# design.net
KiCad netlist of a schematic drawn in Altium Designer
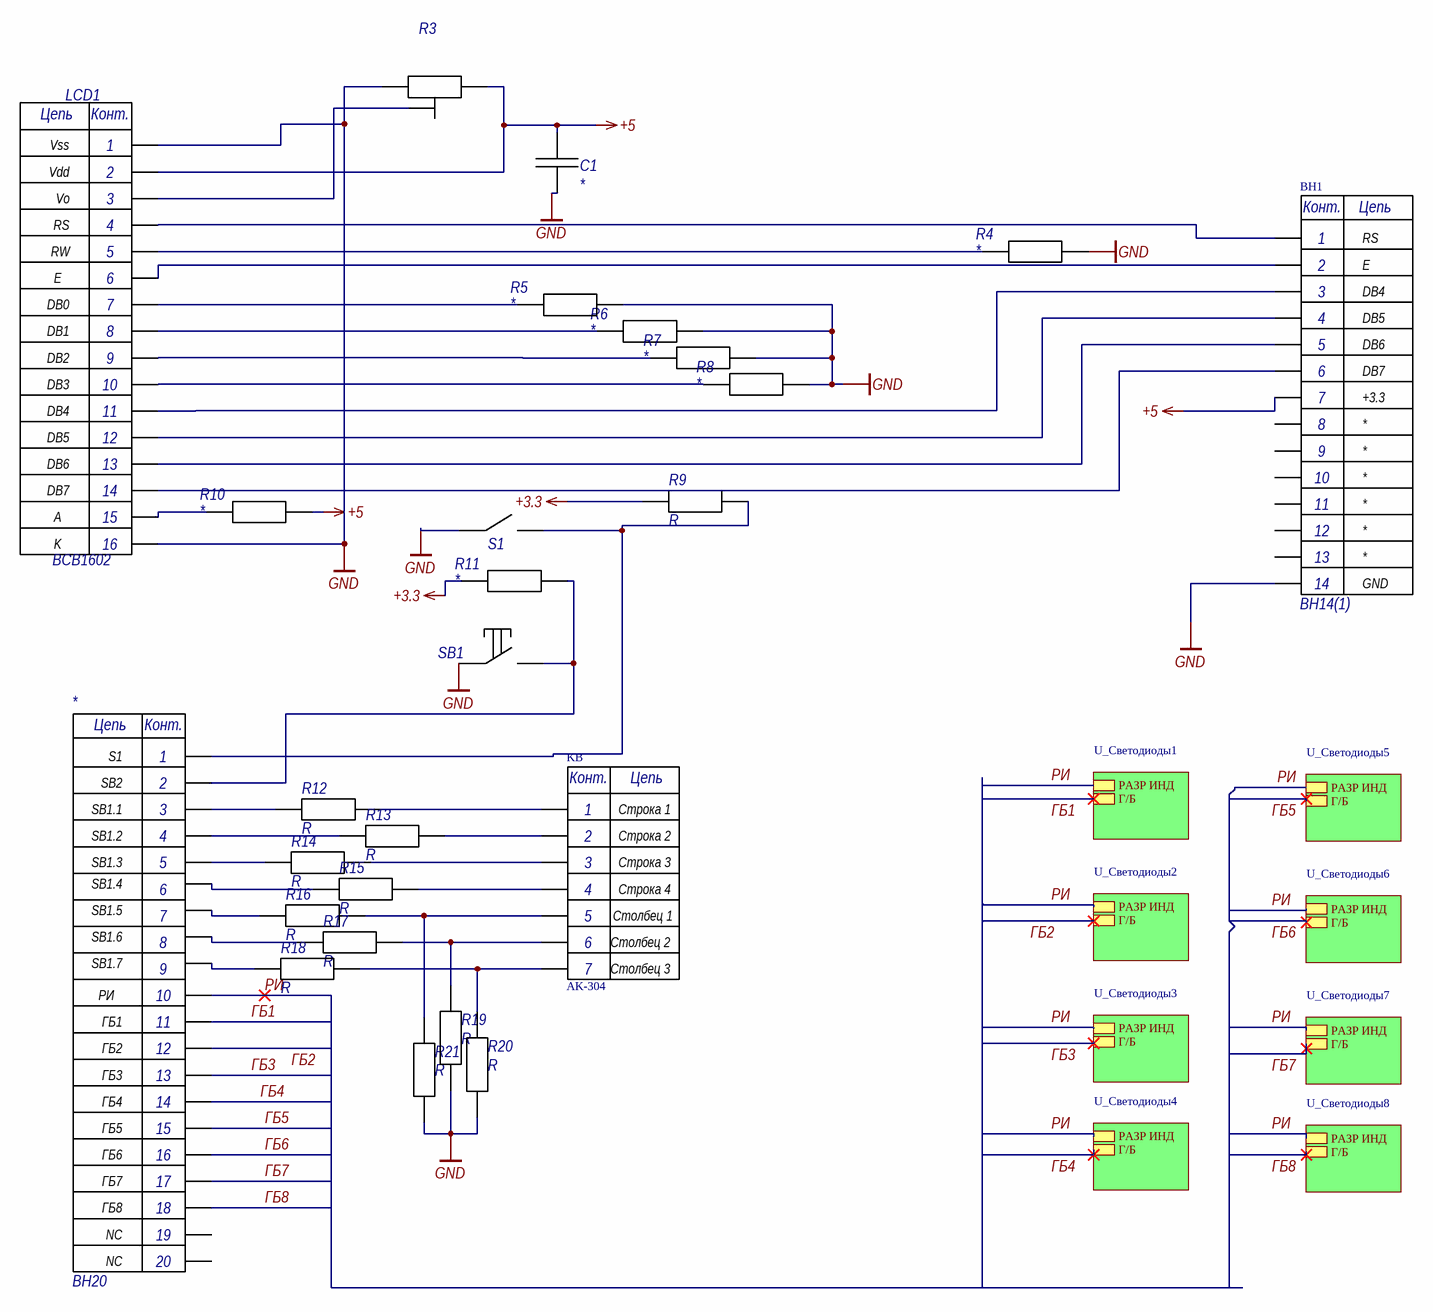
[diagram p0: Управление (дисплей+клавиатура).SchDoc]

(export (version "E")
  (design (tool "Eeschema 10.0.6"))
  (components
    (comp (ref "*") (value "BH20") (footprint "IDC20") (libsource (lib "УГО") (part "BH20")))
    (comp (ref "BH1")
      (value "BH14(1)")
      (footprint "BH-14 (DS1013-14S) (IDC-14MS)")
      (libsource (lib "UGO") (part "BH14(3)"))
    )
    (comp (ref "C1") (value "*") (footprint "C(ceramic)") (libsource (lib "*") (part "C(ceramic)")))
    (comp (ref "KB") (value "AK-304") (footprint "AK-304-N-BBW") (libsource (lib "УГО") (part "AK-304")))
    (comp (ref "LCD1") (value "BCB1602") (footprint "BCB1602") (libsource (lib "*") (part "BCB1602")))
    (comp (ref "R3") (value "~") (footprint "R(подстр)") (libsource (lib "*") (part "R(подстр)")))
    (comp (ref "R4") (value "*") (footprint "R") (libsource (lib "*") (part "R")))
    (comp (ref "R5") (value "*") (footprint "R") (libsource (lib "*") (part "R")))
    (comp (ref "R6") (value "*") (footprint "R") (libsource (lib "*") (part "R")))
    (comp (ref "R7") (value "*") (footprint "R") (libsource (lib "*") (part "R")))
    (comp (ref "R8") (value "*") (footprint "R") (libsource (lib "*") (part "R")))
    (comp (ref "R9") (value "R") (footprint "R") (libsource (lib "UGO") (part "R")))
    (comp (ref "R10") (value "*") (footprint "R") (libsource (lib "*") (part "R")))
    (comp (ref "R11") (value "*") (footprint "R") (libsource (lib "*") (part "R")))
    (comp (ref "R12") (value "R") (footprint "R") (libsource (lib "UGO") (part "R")))
    (comp (ref "R13") (value "R") (footprint "R") (libsource (lib "UGO") (part "R")))
    (comp (ref "R14") (value "R") (footprint "R") (libsource (lib "UGO") (part "R")))
    (comp (ref "R15") (value "R") (footprint "R") (libsource (lib "UGO") (part "R")))
    (comp (ref "R16") (value "R") (footprint "R") (libsource (lib "UGO") (part "R")))
    (comp (ref "R17") (value "R") (footprint "R") (libsource (lib "UGO") (part "R")))
    (comp (ref "R18") (value "R") (footprint "R") (libsource (lib "UGO") (part "R")))
    (comp (ref "R19") (value "R") (footprint "R") (libsource (lib "") (part "R_1")))
    (comp (ref "R20") (value "R") (footprint "R") (libsource (lib "") (part "R_1")))
    (comp (ref "R21") (value "R") (footprint "R") (libsource (lib "") (part "R_1")))
    (comp (ref "S1") (value "(?)тумблер") (footprint "MTS-2") (libsource (lib "UGO") (part "(?)тумблер")))
    (comp (ref "SB1") (value "ПУСК") (footprint "кнопка") (libsource (lib "UGO") (part "кнопка")))
  )
  (nets
    (net (code "1") (name "+3.3") (class "Default")
      (node (ref "R11") (pin "1") (pintype "passive"))
      (node (ref "R9") (pin "1") (pintype "passive"))
    )
    (net (code "2") (name "+5") (class "Default")
      (node (ref "BH1") (pin "7") (pinfunction "+3.3_7") (pintype "passive"))
      (node (ref "C1") (pin "2") (pintype "passive"))
      (node (ref "LCD1") (pin "2") (pinfunction "Vdd_2") (pintype "passive"))
      (node (ref "R10") (pin "2") (pintype "passive"))
      (node (ref "R3") (pin "1") (pintype "passive"))
    )
    (net (code "3") (name "/ГБ1") (class "Default")
      (node (ref "*") (pin "11") (pinfunction "ГБ1_11") (pintype "passive+no_connect"))
    )
    (net (code "4") (name "/ГБ2") (class "Default")
      (node (ref "*") (pin "12") (pinfunction "ГБ2_12") (pintype "passive+no_connect"))
    )
    (net (code "5") (name "/ГБ3") (class "Default")
      (node (ref "*") (pin "13") (pinfunction "ГБ3_13") (pintype "passive"))
    )
    (net (code "6") (name "/ГБ4") (class "Default")
      (node (ref "*") (pin "14") (pinfunction "ГБ4_14") (pintype "passive"))
    )
    (net (code "7") (name "/ГБ5") (class "Default")
      (node (ref "*") (pin "15") (pinfunction "ГБ5_15") (pintype "passive+no_connect"))
    )
    (net (code "8") (name "/ГБ6") (class "Default")
      (node (ref "*") (pin "16") (pinfunction "ГБ6_16") (pintype "passive+no_connect"))
    )
    (net (code "9") (name "/ГБ7") (class "Default")
      (node (ref "*") (pin "17") (pinfunction "ГБ7_17") (pintype "passive"))
    )
    (net (code "10") (name "/ГБ8") (class "Default")
      (node (ref "*") (pin "18") (pinfunction "ГБ8_18") (pintype "passive"))
    )
    (net (code "12") (name "/РИ") (class "Default")
      (node (ref "*") (pin "10") (pinfunction "РИ_10") (pintype "passive"))
    )
    (net (code "13") (name "GND") (class "Default")
      (node (ref "BH1") (pin "14") (pinfunction "GND_14") (pintype "passive"))
      (node (ref "C1") (pin "1") (pintype "passive"))
      (node (ref "LCD1") (pin "1") (pinfunction "Vss_1") (pintype "passive"))
      (node (ref "LCD1") (pin "16") (pinfunction "K_16") (pintype "passive"))
      (node (ref "R19") (pin "1") (pintype "passive"))
      (node (ref "R20") (pin "1") (pintype "passive"))
      (node (ref "R21") (pin "1") (pintype "passive"))
      (node (ref "R3") (pin "2") (pintype "passive"))
      (node (ref "R4") (pin "2") (pintype "passive"))
      (node (ref "R5") (pin "2") (pintype "passive"))
      (node (ref "R6") (pin "2") (pintype "passive"))
      (node (ref "R7") (pin "2") (pintype "passive"))
      (node (ref "R8") (pin "2") (pintype "passive"))
      (node (ref "S1") (pin "1") (pintype "passive"))
      (node (ref "SB1") (pin "1") (pintype "passive"))
    )
    (net (code "14") (name "Net-(*-S1)") (class "Default")
      (node (ref "*") (pin "1") (pinfunction "S1_1") (pintype "passive"))
      (node (ref "R9") (pin "2") (pintype "passive"))
      (node (ref "S1") (pin "2") (pintype "passive"))
    )
    (net (code "15") (name "Net-(*-SB1.1)") (class "Default")
      (node (ref "*") (pin "3") (pinfunction "SB1.1_3") (pintype "passive"))
      (node (ref "R12") (pin "1") (pintype "passive"))
    )
    (net (code "16") (name "Net-(*-SB1.2)") (class "Default")
      (node (ref "*") (pin "4") (pinfunction "SB1.2_4") (pintype "passive"))
      (node (ref "R13") (pin "1") (pintype "passive"))
    )
    (net (code "17") (name "Net-(*-SB1.3)") (class "Default")
      (node (ref "*") (pin "5") (pinfunction "SB1.3_5") (pintype "passive"))
      (node (ref "R14") (pin "1") (pintype "passive"))
    )
    (net (code "18") (name "Net-(*-SB1.4)") (class "Default")
      (node (ref "*") (pin "6") (pinfunction "SB1.4_6") (pintype "passive"))
      (node (ref "R15") (pin "1") (pintype "passive"))
    )
    (net (code "19") (name "Net-(*-SB1.5)") (class "Default")
      (node (ref "*") (pin "7") (pinfunction "SB1.5_7") (pintype "passive"))
      (node (ref "R16") (pin "1") (pintype "passive"))
    )
    (net (code "20") (name "Net-(*-SB1.6)") (class "Default")
      (node (ref "*") (pin "8") (pinfunction "SB1.6_8") (pintype "passive"))
      (node (ref "R17") (pin "1") (pintype "passive"))
    )
    (net (code "21") (name "Net-(*-SB1.7)") (class "Default")
      (node (ref "*") (pin "9") (pinfunction "SB1.7_9") (pintype "passive"))
      (node (ref "R18") (pin "1") (pintype "passive"))
    )
    (net (code "22") (name "Net-(*-SB2)") (class "Default")
      (node (ref "*") (pin "2") (pinfunction "SB2_2") (pintype "passive"))
      (node (ref "R11") (pin "2") (pintype "passive"))
      (node (ref "SB1") (pin "2") (pintype "passive"))
    )
    (net (code "23") (name "Net-(BH1-DB4)") (class "Default")
      (node (ref "BH1") (pin "3") (pinfunction "DB4_3") (pintype "passive"))
      (node (ref "LCD1") (pin "11") (pinfunction "DB4_11") (pintype "passive"))
    )
    (net (code "24") (name "Net-(BH1-DB5)") (class "Default")
      (node (ref "BH1") (pin "4") (pinfunction "DB5_4") (pintype "passive"))
      (node (ref "LCD1") (pin "12") (pinfunction "DB5_12") (pintype "passive"))
    )
    (net (code "25") (name "Net-(BH1-DB6)") (class "Default")
      (node (ref "BH1") (pin "5") (pinfunction "DB6_5") (pintype "passive"))
      (node (ref "LCD1") (pin "13") (pinfunction "DB6_13") (pintype "passive"))
    )
    (net (code "26") (name "Net-(BH1-DB7)") (class "Default")
      (node (ref "BH1") (pin "6") (pinfunction "DB7_6") (pintype "passive"))
      (node (ref "LCD1") (pin "14") (pinfunction "DB7_14") (pintype "passive"))
    )
    (net (code "27") (name "Net-(BH1-E)") (class "Default")
      (node (ref "BH1") (pin "2") (pinfunction "E_2") (pintype "passive"))
      (node (ref "LCD1") (pin "6") (pinfunction "E_6") (pintype "passive"))
    )
    (net (code "28") (name "Net-(BH1-RS)") (class "Default")
      (node (ref "BH1") (pin "1") (pinfunction "RS_1") (pintype "passive"))
      (node (ref "LCD1") (pin "4") (pinfunction "RS_4") (pintype "passive"))
    )
    (net (code "29") (name "Net-(KB-Столбец_1)") (class "Default")
      (node (ref "KB") (pin "5") (pinfunction "Столбец_1_5") (pintype "passive"))
      (node (ref "R16") (pin "2") (pintype "passive"))
      (node (ref "R21") (pin "2") (pintype "passive"))
    )
    (net (code "30") (name "Net-(KB-Столбец_2)") (class "Default")
      (node (ref "KB") (pin "6") (pinfunction "Столбец_2_6") (pintype "passive"))
      (node (ref "R17") (pin "2") (pintype "passive"))
      (node (ref "R19") (pin "2") (pintype "passive"))
    )
    (net (code "31") (name "Net-(KB-Столбец_3)") (class "Default")
      (node (ref "KB") (pin "7") (pinfunction "Столбец_3_7") (pintype "passive"))
      (node (ref "R18") (pin "2") (pintype "passive"))
      (node (ref "R20") (pin "2") (pintype "passive"))
    )
    (net (code "32") (name "Net-(KB-Строка_1)") (class "Default")
      (node (ref "KB") (pin "1") (pinfunction "Строка_1_1") (pintype "passive"))
      (node (ref "R12") (pin "2") (pintype "passive"))
    )
    (net (code "33") (name "Net-(KB-Строка_2)") (class "Default")
      (node (ref "KB") (pin "2") (pinfunction "Строка_2_2") (pintype "passive"))
      (node (ref "R13") (pin "2") (pintype "passive"))
    )
    (net (code "34") (name "Net-(KB-Строка_3)") (class "Default")
      (node (ref "KB") (pin "3") (pinfunction "Строка_3_3") (pintype "passive"))
      (node (ref "R14") (pin "2") (pintype "passive"))
    )
    (net (code "35") (name "Net-(KB-Строка_4)") (class "Default")
      (node (ref "KB") (pin "4") (pinfunction "Строка_4_4") (pintype "passive"))
      (node (ref "R15") (pin "2") (pintype "passive"))
    )
    (net (code "36") (name "Net-(LCD1-A)") (class "Default")
      (node (ref "LCD1") (pin "15") (pinfunction "A_15") (pintype "passive"))
      (node (ref "R10") (pin "1") (pintype "passive"))
    )
    (net (code "37") (name "Net-(LCD1-DB0)") (class "Default")
      (node (ref "LCD1") (pin "7") (pinfunction "DB0_7") (pintype "passive"))
      (node (ref "R5") (pin "1") (pintype "passive"))
    )
    (net (code "38") (name "Net-(LCD1-DB1)") (class "Default")
      (node (ref "LCD1") (pin "8") (pinfunction "DB1_8") (pintype "passive"))
      (node (ref "R6") (pin "1") (pintype "passive"))
    )
    (net (code "39") (name "Net-(LCD1-DB2)") (class "Default")
      (node (ref "LCD1") (pin "9") (pinfunction "DB2_9") (pintype "passive"))
      (node (ref "R7") (pin "1") (pintype "passive"))
    )
    (net (code "40") (name "Net-(LCD1-DB3)") (class "Default")
      (node (ref "LCD1") (pin "10") (pinfunction "DB3_10") (pintype "passive"))
      (node (ref "R8") (pin "1") (pintype "passive"))
    )
    (net (code "41") (name "Net-(LCD1-RW)") (class "Default")
      (node (ref "LCD1") (pin "5") (pinfunction "RW_5") (pintype "passive"))
      (node (ref "R4") (pin "1") (pintype "passive"))
    )
    (net (code "42") (name "Net-(LCD1-Vo)") (class "Default")
      (node (ref "LCD1") (pin "3") (pinfunction "Vo_3") (pintype "passive"))
      (node (ref "R3") (pin "3") (pintype "passive"))
    )
    (net (code "43") (name "unconnected-(*-NC-Pad19)") (class "Default")
      (node (ref "*") (pin "19") (pinfunction "NC_19") (pintype "passive"))
    )
    (net (code "44") (name "unconnected-(*-NC-Pad20)") (class "Default")
      (node (ref "*") (pin "20") (pinfunction "NC_20") (pintype "passive"))
    )
    (net (code "45") (name "unconnected-(BH1-*-Pad8)") (class "Default")
      (node (ref "BH1") (pin "8") (pinfunction "*_8") (pintype "passive"))
    )
    (net (code "46") (name "unconnected-(BH1-*-Pad9)") (class "Default")
      (node (ref "BH1") (pin "9") (pinfunction "*_9") (pintype "passive"))
    )
    (net (code "47") (name "unconnected-(BH1-*-Pad10)") (class "Default")
      (node (ref "BH1") (pin "10") (pinfunction "*_10") (pintype "passive"))
    )
    (net (code "48") (name "unconnected-(BH1-*-Pad11)") (class "Default")
      (node (ref "BH1") (pin "11") (pinfunction "*_11") (pintype "passive"))
    )
    (net (code "49") (name "unconnected-(BH1-*-Pad12)") (class "Default")
      (node (ref "BH1") (pin "12") (pinfunction "*_12") (pintype "passive"))
    )
    (net (code "50") (name "unconnected-(BH1-*-Pad13)") (class "Default")
      (node (ref "BH1") (pin "13") (pinfunction "*_13") (pintype "passive"))
    )
  )
)
